# CervusShield_io.net
KiCad netlist of a schematic drawn in EAGLE
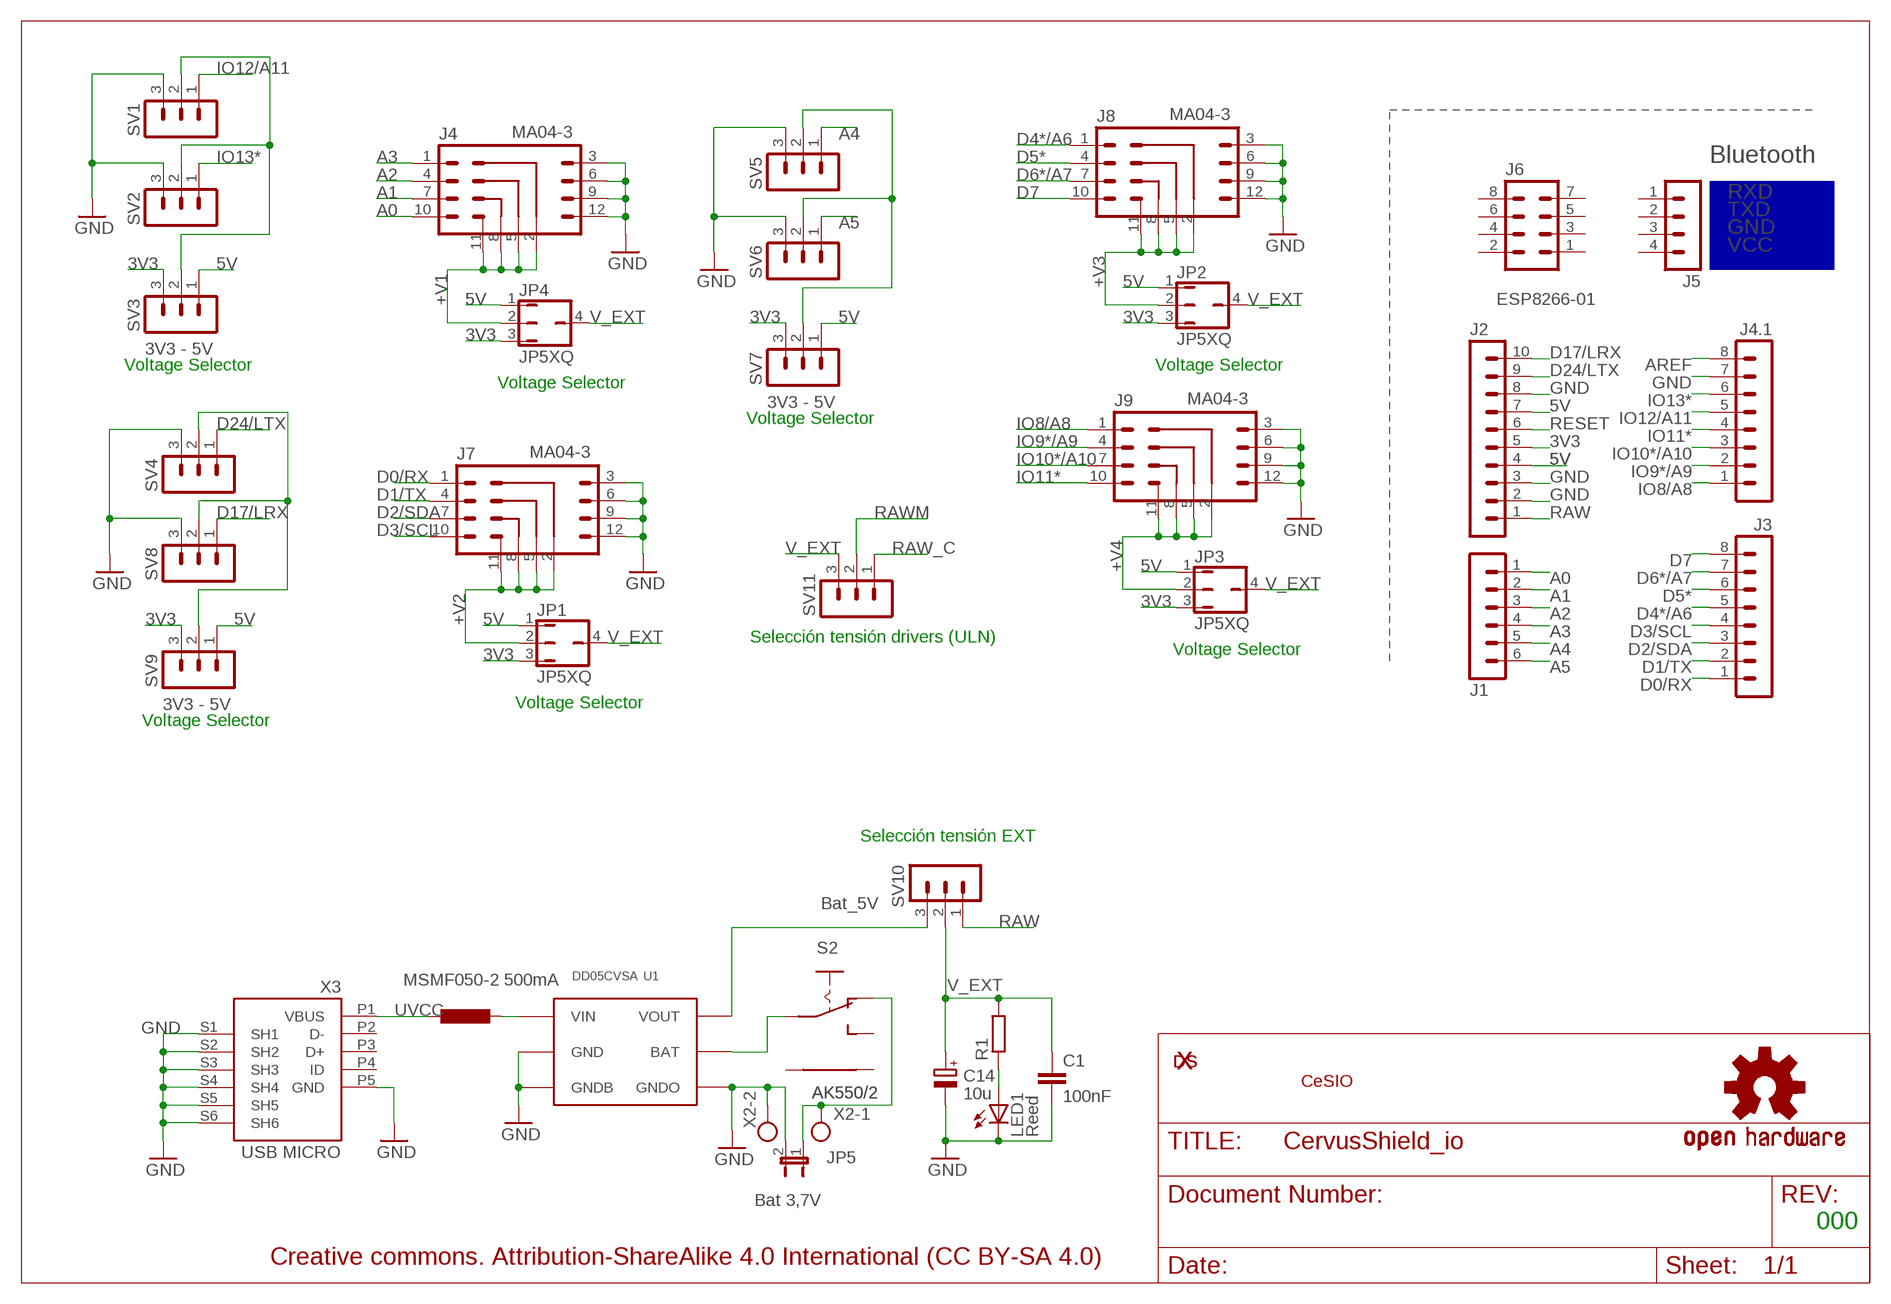
[diagram p0: schematic, sheet 1]

(export (version "E")
  (design (tool "Eeschema 10.0.6"))
  (components
    (comp (ref "C1")
      (value "100nF")
      (footprint "eagle-import:C0603")
      (libsource (lib "eagle-import") (part "C-EUC0603"))
    )
    (comp (ref "C14")
      (value "10u")
      (footprint "eagle-import:SMC_B")
      (libsource (lib "eagle-import") (part "CPOL-EUSMCB"))
    )
    (comp (ref "F1")
      (value "MSMF050-2 500mA")
      (footprint "eagle-import:L1812")
      (libsource (lib "eagle-import") (part "L-EUL1812"))
    )
    (comp (ref "J1")
      (value "Connector, 2.54 mm, 1x6 Contacts, Receptacle")
      (footprint "eagle-import:MA06-1")
      (libsource (lib "eagle-import") (part "MA06-1"))
    )
    (comp (ref "J2")
      (value "Connector, Vertical 2.54 mm, 1x10 Contacts, Receptacle")
      (footprint "eagle-import:MA10-1")
      (libsource (lib "eagle-import") (part "MA10-1"))
    )
    (comp (ref "J3")
      (value "Connector, Vertical, 2.54 mm, 8 Contacts, Receptacle")
      (footprint "eagle-import:MA08-1")
      (libsource (lib "eagle-import") (part "MA08-1"))
    )
    (comp (ref "J4")
      (value "MA04-3")
      (footprint "eagle-import:MA04-3")
      (libsource (lib "eagle-import") (part "MA04-3"))
    )
    (comp (ref "J4.1")
      (value "Connector, Vertical, 2.54 mm, 8 Contacts, Receptacle")
      (footprint "eagle-import:MA08-1")
      (libsource (lib "eagle-import") (part "MA08-1"))
    )
    (comp (ref "J5")
      (value "Connector, Vertical, 2.54 mm, 1x4 Contacts, Receptacle")
      (footprint "eagle-import:MA04-1")
      (libsource (lib "eagle-import") (part "MA04-1"))
    )
    (comp (ref "J6")
      (value "Connector, Vertical, 2.54 mm, 2x4 (8) Contacts, Receptacle")
      (footprint "eagle-import:MA04-2")
      (libsource (lib "eagle-import") (part "MA04-2"))
    )
    (comp (ref "J7")
      (value "MA04-3")
      (footprint "eagle-import:MA04-3")
      (libsource (lib "eagle-import") (part "MA04-3"))
    )
    (comp (ref "J8")
      (value "MA04-3")
      (footprint "eagle-import:MA04-3")
      (libsource (lib "eagle-import") (part "MA04-3"))
    )
    (comp (ref "J9")
      (value "MA04-3")
      (footprint "eagle-import:MA04-3")
      (libsource (lib "eagle-import") (part "MA04-3"))
    )
    (comp (ref "JP1")
      (value "JP5XQ")
      (footprint "eagle-import:JP5XQ")
      (libsource (lib "eagle-import") (part "JP5XQ"))
    )
    (comp (ref "JP2")
      (value "JP5XQ")
      (footprint "eagle-import:JP5XQ")
      (libsource (lib "eagle-import") (part "JP5XQ"))
    )
    (comp (ref "JP3")
      (value "JP5XQ")
      (footprint "eagle-import:JP5XQ")
      (libsource (lib "eagle-import") (part "JP5XQ"))
    )
    (comp (ref "JP4")
      (value "JP5XQ")
      (footprint "eagle-import:JP5XQ")
      (libsource (lib "eagle-import") (part "JP5XQ"))
    )
    (comp (ref "JP5")
      (value "JP1E")
      (footprint "eagle-import:JP1")
      (libsource (lib "eagle-import") (part "JP1E"))
    )
    (comp (ref "LED1")
      (value "Reed")
      (footprint "eagle-import:CHIPLED_0603")
      (libsource (lib "eagle-import") (part "LEDCHIPLED_0603"))
    )
    (comp (ref "LOGO1")
      (value "OSHW-LOGOS")
      (footprint "eagle-import:OSHW-LOGO-S")
      (libsource (lib "eagle-import") (part "OSHW-LOGOS"))
    )
    (comp (ref "R1")
      (value "R-EU_R0603")
      (footprint "eagle-import:R0603")
      (libsource (lib "eagle-import") (part "R-EU_R0603"))
    )
    (comp (ref "S2")
      (value "ESCORNA_SK12F14D")
      (footprint "eagle-import:ESCORNA_SK-12D07")
      (libsource (lib "eagle-import") (part "ESCORNA_SK12F14D"))
    )
    (comp (ref "SV1")
      (value "MA03-1")
      (footprint "eagle-import:MA03-1")
      (libsource (lib "eagle-import") (part "MA03-1"))
    )
    (comp (ref "SV2")
      (value "MA03-1")
      (footprint "eagle-import:MA03-1")
      (libsource (lib "eagle-import") (part "MA03-1"))
    )
    (comp (ref "SV3")
      (value "MA03-1")
      (footprint "eagle-import:MA03-1")
      (libsource (lib "eagle-import") (part "MA03-1"))
    )
    (comp (ref "SV4")
      (value "MA03-1")
      (footprint "eagle-import:MA03-1")
      (libsource (lib "eagle-import") (part "MA03-1"))
    )
    (comp (ref "SV5")
      (value "MA03-1")
      (footprint "eagle-import:MA03-1")
      (libsource (lib "eagle-import") (part "MA03-1"))
    )
    (comp (ref "SV6")
      (value "MA03-1")
      (footprint "eagle-import:MA03-1")
      (libsource (lib "eagle-import") (part "MA03-1"))
    )
    (comp (ref "SV7")
      (value "MA03-1")
      (footprint "eagle-import:MA03-1")
      (libsource (lib "eagle-import") (part "MA03-1"))
    )
    (comp (ref "SV8")
      (value "MA03-1")
      (footprint "eagle-import:MA03-1")
      (libsource (lib "eagle-import") (part "MA03-1"))
    )
    (comp (ref "SV9")
      (value "MA03-1")
      (footprint "eagle-import:MA03-1")
      (libsource (lib "eagle-import") (part "MA03-1"))
    )
    (comp (ref "SV10")
      (value "MA03-1")
      (footprint "eagle-import:MA03-1")
      (libsource (lib "eagle-import") (part "MA03-1"))
    )
    (comp (ref "SV11")
      (value "MA03-1")
      (footprint "eagle-import:MA03-1")
      (libsource (lib "eagle-import") (part "MA03-1"))
    )
    (comp (ref "U$1")
      (value "XDESIG")
      (footprint "eagle-import:XDESIG_CU_2")
      (libsource (lib "eagle-import") (part "XDESIG"))
    )
    (comp (ref "U$3")
      (value "XDESIG")
      (footprint "eagle-import:XDESIG_CU_2")
      (libsource (lib "eagle-import") (part "XDESIG"))
    )
    (comp (ref "U1")
      (value "DD05CVSA")
      (footprint "eagle-import:DD05CVSA")
      (libsource (lib "eagle-import") (part "DD05CVSA"))
    )
    (comp (ref "X2")
      (value "AK550/2")
      (footprint "eagle-import:AK550_2")
      (libsource (lib "eagle-import") (part "AK550/2"))
    )
    (comp (ref "X3")
      (value "USB MICRO")
      (footprint "eagle-import:CON2_USB_MICRO_B_AT")
      (libsource (lib "eagle-import") (part "MYCON2_USB-MINI-B"))
    )
  )
  (nets
    (net (code "1") (name "/+V1") (class "Default")
      (node (ref "J4") (pin "11") (pinfunction "11_11") (pintype "passive"))
      (node (ref "J4") (pin "2") (pinfunction "2_2") (pintype "passive"))
      (node (ref "J4") (pin "5") (pinfunction "5_5") (pintype "passive"))
      (node (ref "J4") (pin "8") (pinfunction "8_8") (pintype "passive"))
      (node (ref "JP4") (pin "2") (pinfunction "2_2") (pintype "passive"))
    )
    (net (code "2") (name "/+V2") (class "Default")
      (node (ref "J7") (pin "11") (pinfunction "11_11") (pintype "passive"))
      (node (ref "J7") (pin "2") (pinfunction "2_2") (pintype "passive"))
      (node (ref "J7") (pin "5") (pinfunction "5_5") (pintype "passive"))
      (node (ref "J7") (pin "8") (pinfunction "8_8") (pintype "passive"))
      (node (ref "JP1") (pin "2") (pinfunction "2_2") (pintype "passive"))
    )
    (net (code "3") (name "/+V3") (class "Default")
      (node (ref "J8") (pin "11") (pinfunction "11_11") (pintype "passive"))
      (node (ref "J8") (pin "2") (pinfunction "2_2") (pintype "passive"))
      (node (ref "J8") (pin "5") (pinfunction "5_5") (pintype "passive"))
      (node (ref "J8") (pin "8") (pinfunction "8_8") (pintype "passive"))
      (node (ref "JP2") (pin "2") (pinfunction "2_2") (pintype "passive"))
    )
    (net (code "4") (name "/+V4") (class "Default")
      (node (ref "J9") (pin "11") (pinfunction "11_11") (pintype "passive"))
      (node (ref "J9") (pin "2") (pinfunction "2_2") (pintype "passive"))
      (node (ref "J9") (pin "5") (pinfunction "5_5") (pintype "passive"))
      (node (ref "J9") (pin "8") (pinfunction "8_8") (pintype "passive"))
      (node (ref "JP3") (pin "2") (pinfunction "2_2") (pintype "passive"))
    )
    (net (code "5") (name "/3V3") (class "Default")
      (node (ref "J2") (pin "5") (pinfunction "5_5") (pintype "passive"))
      (node (ref "JP1") (pin "3") (pinfunction "3_3") (pintype "passive"))
      (node (ref "JP2") (pin "3") (pinfunction "3_3") (pintype "passive"))
      (node (ref "JP3") (pin "3") (pinfunction "3_3") (pintype "passive"))
      (node (ref "JP4") (pin "3") (pinfunction "3_3") (pintype "passive"))
      (node (ref "SV3") (pin "3") (pinfunction "3_3") (pintype "passive"))
      (node (ref "SV7") (pin "3") (pinfunction "3_3") (pintype "passive"))
      (node (ref "SV9") (pin "3") (pinfunction "3_3") (pintype "passive"))
    )
    (net (code "6") (name "/5V") (class "Default")
      (node (ref "J2") (pin "4") (pinfunction "4_4") (pintype "passive"))
      (node (ref "J2") (pin "7") (pinfunction "7_7") (pintype "passive"))
      (node (ref "JP1") (pin "1") (pinfunction "1_1") (pintype "passive"))
      (node (ref "JP2") (pin "1") (pinfunction "1_1") (pintype "passive"))
      (node (ref "JP3") (pin "1") (pinfunction "1_1") (pintype "passive"))
      (node (ref "JP4") (pin "1") (pinfunction "1_1") (pintype "passive"))
      (node (ref "SV3") (pin "1") (pinfunction "1_1") (pintype "passive"))
      (node (ref "SV7") (pin "1") (pinfunction "1_1") (pintype "passive"))
      (node (ref "SV9") (pin "1") (pinfunction "1_1") (pintype "passive"))
    )
    (net (code "7") (name "/A0") (class "Default")
      (node (ref "J1") (pin "1") (pinfunction "1_1") (pintype "passive"))
      (node (ref "J4") (pin "10") (pinfunction "10_10") (pintype "passive"))
    )
    (net (code "8") (name "/A1") (class "Default")
      (node (ref "J1") (pin "2") (pinfunction "2_2") (pintype "passive"))
      (node (ref "J4") (pin "7") (pinfunction "7_7") (pintype "passive"))
    )
    (net (code "9") (name "/A2") (class "Default")
      (node (ref "J1") (pin "3") (pinfunction "3_3") (pintype "passive"))
      (node (ref "J4") (pin "4") (pinfunction "4_4") (pintype "passive"))
    )
    (net (code "10") (name "/A3") (class "Default")
      (node (ref "J1") (pin "4") (pinfunction "4_4") (pintype "passive"))
      (node (ref "J4") (pin "1") (pinfunction "1_1") (pintype "passive"))
    )
    (net (code "11") (name "/A4") (class "Default")
      (node (ref "J1") (pin "5") (pinfunction "5_5") (pintype "passive"))
      (node (ref "SV5") (pin "1") (pinfunction "1_1") (pintype "passive"))
    )
    (net (code "12") (name "/A5") (class "Default")
      (node (ref "J1") (pin "6") (pinfunction "6_6") (pintype "passive"))
      (node (ref "SV6") (pin "1") (pinfunction "1_1") (pintype "passive"))
    )
    (net (code "13") (name "/AREF") (class "Default")
      (node (ref "J4.1") (pin "8") (pinfunction "8_8") (pintype "passive"))
    )
    (net (code "14") (name "/D0{slash}RX") (class "Default")
      (node (ref "J3") (pin "1") (pinfunction "1_1") (pintype "passive"))
      (node (ref "J7") (pin "1") (pinfunction "1_1") (pintype "passive"))
    )
    (net (code "15") (name "/D1{slash}TX") (class "Default")
      (node (ref "J3") (pin "2") (pinfunction "2_2") (pintype "passive"))
      (node (ref "J7") (pin "4") (pinfunction "4_4") (pintype "passive"))
    )
    (net (code "16") (name "/D2{slash}SDA") (class "Default")
      (node (ref "J3") (pin "3") (pinfunction "3_3") (pintype "passive"))
      (node (ref "J7") (pin "7") (pinfunction "7_7") (pintype "passive"))
    )
    (net (code "17") (name "/D3{slash}SCL") (class "Default")
      (node (ref "J3") (pin "4") (pinfunction "4_4") (pintype "passive"))
      (node (ref "J7") (pin "10") (pinfunction "10_10") (pintype "passive"))
    )
    (net (code "18") (name "/D4*{slash}A6") (class "Default")
      (node (ref "J3") (pin "5") (pinfunction "5_5") (pintype "passive"))
      (node (ref "J8") (pin "1") (pinfunction "1_1") (pintype "passive"))
    )
    (net (code "19") (name "/D5*") (class "Default")
      (node (ref "J3") (pin "6") (pinfunction "6_6") (pintype "passive"))
      (node (ref "J8") (pin "4") (pinfunction "4_4") (pintype "passive"))
    )
    (net (code "20") (name "/D6*{slash}A7") (class "Default")
      (node (ref "J3") (pin "7") (pinfunction "7_7") (pintype "passive"))
      (node (ref "J8") (pin "7") (pinfunction "7_7") (pintype "passive"))
    )
    (net (code "21") (name "/D7") (class "Default")
      (node (ref "J3") (pin "8") (pinfunction "8_8") (pintype "passive"))
      (node (ref "J8") (pin "10") (pinfunction "10_10") (pintype "passive"))
    )
    (net (code "22") (name "/D17{slash}LRX") (class "Default")
      (node (ref "J2") (pin "10") (pinfunction "10_10") (pintype "passive"))
      (node (ref "SV8") (pin "1") (pinfunction "1_1") (pintype "passive"))
    )
    (net (code "23") (name "/D24{slash}LTX") (class "Default")
      (node (ref "J2") (pin "9") (pinfunction "9_9") (pintype "passive"))
      (node (ref "SV4") (pin "1") (pinfunction "1_1") (pintype "passive"))
    )
    (net (code "24") (name "/IO8{slash}A8") (class "Default")
      (node (ref "J4.1") (pin "1") (pinfunction "1_1") (pintype "passive"))
      (node (ref "J9") (pin "1") (pinfunction "1_1") (pintype "passive"))
    )
    (net (code "25") (name "/IO9*{slash}A9") (class "Default")
      (node (ref "J4.1") (pin "2") (pinfunction "2_2") (pintype "passive"))
      (node (ref "J9") (pin "4") (pinfunction "4_4") (pintype "passive"))
    )
    (net (code "26") (name "/IO10*{slash}A10") (class "Default")
      (node (ref "J4.1") (pin "3") (pinfunction "3_3") (pintype "passive"))
      (node (ref "J9") (pin "7") (pinfunction "7_7") (pintype "passive"))
    )
    (net (code "27") (name "/IO11*") (class "Default")
      (node (ref "J4.1") (pin "4") (pinfunction "4_4") (pintype "passive"))
      (node (ref "J9") (pin "10") (pinfunction "10_10") (pintype "passive"))
    )
    (net (code "28") (name "/IO12{slash}A11") (class "Default")
      (node (ref "J4.1") (pin "5") (pinfunction "5_5") (pintype "passive"))
      (node (ref "SV1") (pin "1") (pinfunction "1_1") (pintype "passive"))
    )
    (net (code "29") (name "/IO13*") (class "Default")
      (node (ref "J4.1") (pin "6") (pinfunction "6_6") (pintype "passive"))
      (node (ref "SV2") (pin "1") (pinfunction "1_1") (pintype "passive"))
    )
    (net (code "30") (name "/RAW") (class "Default")
      (node (ref "J2") (pin "1") (pinfunction "1_1") (pintype "passive"))
      (node (ref "SV10") (pin "1") (pinfunction "1_1") (pintype "passive"))
    )
    (net (code "31") (name "/RAWM") (class "Default")
      (node (ref "SV11") (pin "2") (pinfunction "2_2") (pintype "passive"))
    )
    (net (code "32") (name "/RAW_C") (class "Default")
      (node (ref "SV11") (pin "1") (pinfunction "1_1") (pintype "passive"))
    )
    (net (code "33") (name "/RESET") (class "Default")
      (node (ref "J2") (pin "6") (pinfunction "6_6") (pintype "passive"))
    )
    (net (code "34") (name "/UVCC") (class "Default")
      (node (ref "F1") (pin "2") (pinfunction "2_2") (pintype "passive"))
      (node (ref "X3") (pin "P1") (pinfunction "VBUS_P1") (pintype "power_in"))
    )
    (net (code "35") (name "/V_EXT") (class "Default")
      (node (ref "C1") (pin "1") (pinfunction "1_1") (pintype "passive"))
      (node (ref "C14") (pin "+") (pinfunction "+_+") (pintype "passive"))
      (node (ref "JP1") (pin "4") (pinfunction "4_4") (pintype "passive"))
      (node (ref "JP2") (pin "4") (pinfunction "4_4") (pintype "passive"))
      (node (ref "JP3") (pin "4") (pinfunction "4_4") (pintype "passive"))
      (node (ref "JP4") (pin "4") (pinfunction "4_4") (pintype "passive"))
      (node (ref "R1") (pin "2") (pinfunction "2_2") (pintype "passive"))
      (node (ref "SV10") (pin "2") (pinfunction "2_2") (pintype "passive"))
      (node (ref "SV11") (pin "3") (pinfunction "3_3") (pintype "passive"))
    )
    (net (code "36") (name "GND") (class "Default")
      (node (ref "C1") (pin "2") (pinfunction "2_2") (pintype "passive"))
      (node (ref "C14") (pin "-") (pinfunction "-_-") (pintype "passive"))
      (node (ref "J2") (pin "2") (pinfunction "2_2") (pintype "passive"))
      (node (ref "J2") (pin "3") (pinfunction "3_3") (pintype "passive"))
      (node (ref "J2") (pin "8") (pinfunction "8_8") (pintype "passive"))
      (node (ref "J4") (pin "12") (pinfunction "12_12") (pintype "passive"))
      (node (ref "J4") (pin "3") (pinfunction "3_3") (pintype "passive"))
      (node (ref "J4") (pin "6") (pinfunction "6_6") (pintype "passive"))
      (node (ref "J4") (pin "9") (pinfunction "9_9") (pintype "passive"))
      (node (ref "J4.1") (pin "7") (pinfunction "7_7") (pintype "passive"))
      (node (ref "J7") (pin "12") (pinfunction "12_12") (pintype "passive"))
      (node (ref "J7") (pin "3") (pinfunction "3_3") (pintype "passive"))
      (node (ref "J7") (pin "6") (pinfunction "6_6") (pintype "passive"))
      (node (ref "J7") (pin "9") (pinfunction "9_9") (pintype "passive"))
      (node (ref "J8") (pin "12") (pinfunction "12_12") (pintype "passive"))
      (node (ref "J8") (pin "3") (pinfunction "3_3") (pintype "passive"))
      (node (ref "J8") (pin "6") (pinfunction "6_6") (pintype "passive"))
      (node (ref "J8") (pin "9") (pinfunction "9_9") (pintype "passive"))
      (node (ref "J9") (pin "12") (pinfunction "12_12") (pintype "passive"))
      (node (ref "J9") (pin "3") (pinfunction "3_3") (pintype "passive"))
      (node (ref "J9") (pin "6") (pinfunction "6_6") (pintype "passive"))
      (node (ref "J9") (pin "9") (pinfunction "9_9") (pintype "passive"))
      (node (ref "JP5") (pin "2") (pinfunction "2_2") (pintype "passive"))
      (node (ref "LED1") (pin "C") (pinfunction "C_C") (pintype "passive"))
      (node (ref "SV1") (pin "3") (pinfunction "3_3") (pintype "passive"))
      (node (ref "SV2") (pin "3") (pinfunction "3_3") (pintype "passive"))
      (node (ref "SV4") (pin "3") (pinfunction "3_3") (pintype "passive"))
      (node (ref "SV5") (pin "3") (pinfunction "3_3") (pintype "passive"))
      (node (ref "SV6") (pin "3") (pinfunction "3_3") (pintype "passive"))
      (node (ref "SV8") (pin "3") (pinfunction "3_3") (pintype "passive"))
      (node (ref "U1") (pin "P$2") (pinfunction "GND_P$2") (pintype "bidirectional"))
      (node (ref "U1") (pin "P$4") (pinfunction "GNDB_P$4") (pintype "bidirectional"))
      (node (ref "U1") (pin "P$5") (pinfunction "GNDO_P$5") (pintype "bidirectional"))
      (node (ref "X2") (pin "2") (pinfunction "KL_2") (pintype "passive"))
      (node (ref "X3") (pin "P5") (pinfunction "GND_P5") (pintype "passive"))
      (node (ref "X3") (pin "S1") (pinfunction "SH1_S1") (pintype "passive"))
      (node (ref "X3") (pin "S2") (pinfunction "SH2_S2") (pintype "passive"))
      (node (ref "X3") (pin "S3") (pinfunction "SH3_S3") (pintype "passive"))
      (node (ref "X3") (pin "S4") (pinfunction "SH4_S4") (pintype "passive"))
      (node (ref "X3") (pin "S5") (pinfunction "SH5_S5") (pintype "passive"))
      (node (ref "X3") (pin "S6") (pinfunction "SH6_S6") (pintype "passive"))
    )
    (net (code "37") (name "Net-(LED1-PadA)") (class "Default")
      (node (ref "LED1") (pin "A") (pinfunction "A_A") (pintype "passive"))
      (node (ref "R1") (pin "1") (pinfunction "1_1") (pintype "passive"))
    )
    (net (code "38") (name "Net-(S2-O)") (class "Default")
      (node (ref "JP5") (pin "1") (pinfunction "1_1") (pintype "passive"))
      (node (ref "S2") (pin "P$2") (pinfunction "O_P$2") (pintype "passive"))
      (node (ref "X2") (pin "1") (pinfunction "KL_1") (pintype "passive"))
    )
    (net (code "39") (name "Net-(S2-P)") (class "Default")
      (node (ref "S2") (pin "P$1") (pinfunction "P_P$1") (pintype "passive"))
      (node (ref "U1") (pin "P$3") (pinfunction "BAT_P$3") (pintype "bidirectional"))
    )
    (net (code "40") (name "Net-(SV1-Pad2)") (class "Default")
      (node (ref "SV1") (pin "2") (pinfunction "2_2") (pintype "passive"))
      (node (ref "SV2") (pin "2") (pinfunction "2_2") (pintype "passive"))
      (node (ref "SV3") (pin "2") (pinfunction "2_2") (pintype "passive"))
    )
    (net (code "41") (name "Net-(SV4-Pad2)") (class "Default")
      (node (ref "SV4") (pin "2") (pinfunction "2_2") (pintype "passive"))
      (node (ref "SV8") (pin "2") (pinfunction "2_2") (pintype "passive"))
      (node (ref "SV9") (pin "2") (pinfunction "2_2") (pintype "passive"))
    )
    (net (code "42") (name "Net-(SV5-Pad2)") (class "Default")
      (node (ref "SV5") (pin "2") (pinfunction "2_2") (pintype "passive"))
      (node (ref "SV6") (pin "2") (pinfunction "2_2") (pintype "passive"))
      (node (ref "SV7") (pin "2") (pinfunction "2_2") (pintype "passive"))
    )
    (net (code "43") (name "Net-(U1-VIN)") (class "Default")
      (node (ref "F1") (pin "1") (pinfunction "1_1") (pintype "passive"))
      (node (ref "U1") (pin "P$1") (pinfunction "VIN_P$1") (pintype "bidirectional"))
    )
    (net (code "44") (name "Net-(U1-VOUT)") (class "Default")
      (node (ref "SV10") (pin "3") (pinfunction "3_3") (pintype "passive"))
      (node (ref "U1") (pin "P$6") (pinfunction "VOUT_P$6") (pintype "bidirectional"))
    )
    (net (code "45") (name "unconnected-(J5-Pad1)") (class "Default")
      (node (ref "J5") (pin "1") (pinfunction "1_1") (pintype "passive"))
    )
    (net (code "46") (name "unconnected-(J5-Pad2)") (class "Default")
      (node (ref "J5") (pin "2") (pinfunction "2_2") (pintype "passive"))
    )
    (net (code "47") (name "unconnected-(J5-Pad3)") (class "Default")
      (node (ref "J5") (pin "3") (pinfunction "3_3") (pintype "passive"))
    )
    (net (code "48") (name "unconnected-(J5-Pad4)") (class "Default")
      (node (ref "J5") (pin "4") (pinfunction "4_4") (pintype "passive"))
    )
    (net (code "49") (name "unconnected-(J6-Pad1)") (class "Default")
      (node (ref "J6") (pin "1") (pinfunction "1_1") (pintype "passive"))
    )
    (net (code "50") (name "unconnected-(J6-Pad2)") (class "Default")
      (node (ref "J6") (pin "2") (pinfunction "2_2") (pintype "passive"))
    )
    (net (code "51") (name "unconnected-(J6-Pad3)") (class "Default")
      (node (ref "J6") (pin "3") (pinfunction "3_3") (pintype "passive"))
    )
    (net (code "52") (name "unconnected-(J6-Pad4)") (class "Default")
      (node (ref "J6") (pin "4") (pinfunction "4_4") (pintype "passive"))
    )
    (net (code "53") (name "unconnected-(J6-Pad5)") (class "Default")
      (node (ref "J6") (pin "5") (pinfunction "5_5") (pintype "passive"))
    )
    (net (code "54") (name "unconnected-(J6-Pad6)") (class "Default")
      (node (ref "J6") (pin "6") (pinfunction "6_6") (pintype "passive"))
    )
    (net (code "55") (name "unconnected-(J6-Pad7)") (class "Default")
      (node (ref "J6") (pin "7") (pinfunction "7_7") (pintype "passive"))
    )
    (net (code "56") (name "unconnected-(J6-Pad8)") (class "Default")
      (node (ref "J6") (pin "8") (pinfunction "8_8") (pintype "passive"))
    )
    (net (code "57") (name "unconnected-(S2-P$1-PadP$4)") (class "Default")
      (node (ref "S2") (pin "P$4") (pinfunction "P$1_P$4") (pintype "passive"))
    )
    (net (code "58") (name "unconnected-(S2-P$2-PadP$5)") (class "Default")
      (node (ref "S2") (pin "P$5") (pinfunction "P$2_P$5") (pintype "bidirectional"))
    )
    (net (code "59") (name "unconnected-(S2-S-PadP$3)") (class "Default")
      (node (ref "S2") (pin "P$3") (pinfunction "S_P$3") (pintype "passive"))
    )
    (net (code "60") (name "unconnected-(X3-D+-PadP3)") (class "Default")
      (node (ref "X3") (pin "P3") (pinfunction "D+_P3") (pintype "bidirectional"))
    )
    (net (code "61") (name "unconnected-(X3-D--PadP2)") (class "Default")
      (node (ref "X3") (pin "P2") (pinfunction "D-_P2") (pintype "bidirectional"))
    )
    (net (code "62") (name "unconnected-(X3-ID-PadP4)") (class "Default")
      (node (ref "X3") (pin "P4") (pinfunction "ID_P4") (pintype "bidirectional"))
    )
  )
)
